# PROGRAMMER.net
KiCad netlist of a schematic drawn in Altium Designer
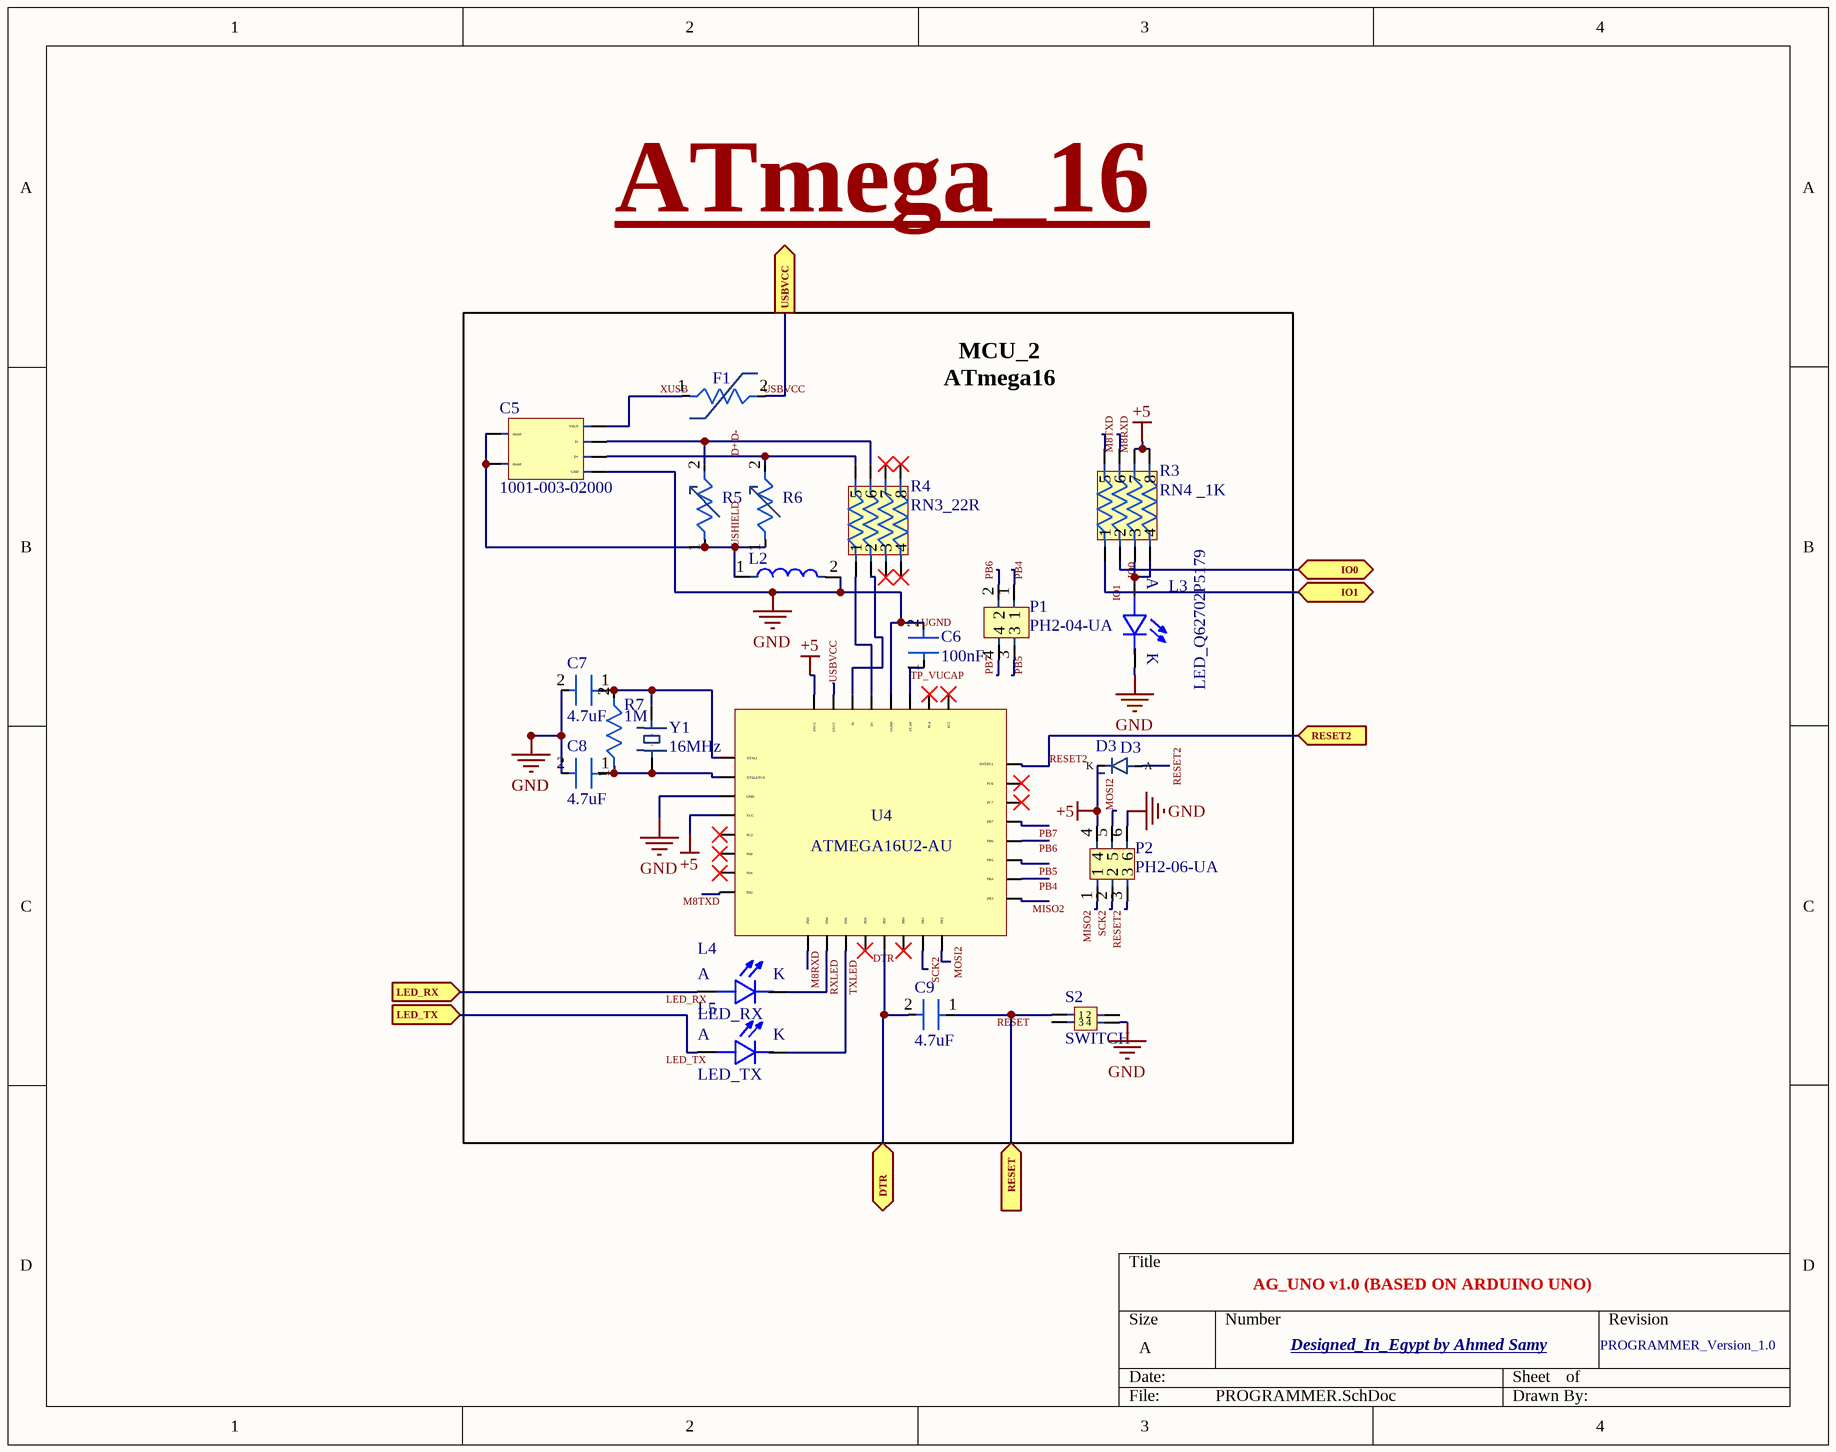
[diagram p0: PROGRAMMER.SchDoc]

(export (version "E")
  (design (tool "Eeschema 10.0.6"))
  (components
    (comp (ref "C5")
      (value "1001-003-02000")
      (footprint "1001-003-02000")
      (description "USB-B (USB TYPE-B) USB 1.1 Receptacle Connector 4 Position Through Hole, Right Angle")
      (libsource (lib "Task") (part "1001-003-02000"))
    )
    (comp (ref "C6")
      (value "100nF")
      (footprint "80-C0805C104M3R")
      (libsource (lib "Task") (part "80-C0805C104M3R"))
    )
    (comp (ref "C7")
      (value "4.7uF")
      (footprint "3372-0805W475K500CCTR-ND")
      (description "CAP.,SMD,0805,X5R,4.7UF,10%,50V")
      (libsource (lib "Task") (part "3372-0805W475K500CCTR-ND"))
    )
    (comp (ref "C8")
      (value "4.7uF")
      (footprint "3372-0805W475K500CCTR-ND")
      (description "CAP.,SMD,0805,X5R,4.7UF,10%,50V")
      (libsource (lib "Task") (part "3372-0805W475K500CCTR-ND"))
    )
    (comp (ref "C9")
      (value "4.7uF")
      (footprint "3372-0805W475K500CCTR-ND")
      (description "CAP.,SMD,0805,X5R,4.7UF,10%,50V")
      (libsource (lib "Task") (part "3372-0805W475K500CCTR-ND"))
    )
    (comp (ref "D3")
      (value "D3")
      (footprint "CD1206-S01575")
      (description "Diode 100 V 150mA Surface Mount 1206 [D2 UNO]")
      (libsource (lib "Task") (part "CD1206-S01575"))
    )
    (comp (ref "F1")
      (value "MF-MSMF050-2")
      (footprint "MF-MSMF050-2")
      (description "Polymeric PTC Resettable Fuse 15V 500 mA Ih Surface Mount 1812 (4532 Metric), Concave [UNO]")
      (libsource (lib "Task") (part "MF-MSMF050-2"))
    )
    (comp (ref "L2")
      (value "BLM21PG300SN1D")
      (footprint "BLM21PG300SN1D")
      (description "30 Ohms @ 100 MHz 1 Power Line Ferrite Bead 0805 (2012 Metric) 4A 14mOhm")
      (libsource (lib "Task") (part "BLM21PG300SN1D"))
    )
    (comp (ref "L3")
      (value "LED_Q62702P5179")
      (footprint "LED_Q62702P5179")
      (description "LED 0805")
      (libsource (lib "Task") (part "LED_Q62702P5179"))
    )
    (comp (ref "L4")
      (value "LED_RX")
      (footprint "LED_Q62702P5179")
      (description "LED 0805")
      (libsource (lib "") (part "LED_Q62702P5179_1"))
    )
    (comp (ref "L5")
      (value "LED_TX")
      (footprint "LED_Q62702P5179")
      (description "LED 0805")
      (libsource (lib "") (part "LED_Q62702P5179_1"))
    )
    (comp (ref "P1")
      (value "PH2-04-UA")
      (footprint "PH2-04-UA")
      (description "Connector Header Through Hole 4 position 0.100\" (2.54mm)")
      (libsource (lib "Task") (part "PH2-04-UA"))
    )
    (comp (ref "P2")
      (value "PH2-06-UA")
      (footprint "PH2-06-UA")
      (description "Connector Header Through Hole 6 position 0.100\" (2.54mm) [ICSP UNO]")
      (libsource (lib "Task") (part "PH2-06-UA"))
    )
    (comp (ref "R3")
      (value "RN4 _1K")
      (footprint "CAY16-103J4GLF")
      (libsource (lib "Task") (part "CAY16-103J4GLF"))
    )
    (comp (ref "R4")
      (value "RN3_22R")
      (footprint "CAY16-103J4GLF")
      (libsource (lib "Task") (part "CAY16-103J4GLF"))
    )
    (comp (ref "R5")
      (value "CG0603MLC-05E")
      (footprint "CG0603MLC-05E")
      (description "Varistor 1 Circuit Surface Mount, MLCV 0603 (1608 Metric)")
      (libsource (lib "Task") (part "CG0603MLC-05E"))
    )
    (comp (ref "R6")
      (value "CG0603MLC-05E")
      (footprint "CG0603MLC-05E")
      (description "Varistor 1 Circuit Surface Mount, MLCV 0603 (1608 Metric)")
      (libsource (lib "Task") (part "CG0603MLC-05E"))
    )
    (comp (ref "R7")
      (value "1M")
      (footprint "CRCW06031M00JNEAC")
      (description "1 MOhms ±5% 0.1W, 1/10W Chip Resistor 0603 (1608 Metric) Thick Film")
      (libsource (lib "Task") (part "CRCW06031M00JNEAC"))
    )
    (comp (ref "S2")
      (value "SWITCH")
      (footprint "B3SL-1002P")
      (description "Tactile Switch SPST-NO Top Actuated Surface Mount")
      (libsource (lib "Task") (part "B3SL-1002P"))
    )
    (comp (ref "U4")
      (value "ATMEGA16U2-AU")
      (footprint "ATMEGA16U2-AU")
      (description "AVR AVR® ATmega Microcontroller IC 8-Bit 16MHz 16KB (8K x 16) FLASH 32-TQFP (7x7)")
      (libsource (lib "Task") (part "ATMEGA16U2-AU"))
    )
    (comp (ref "Y1")
      (value "16MHz")
      (footprint "ECS-160-20-4X-DU")
      (description "16 MHz ±30ppm Crystal 20pF 40 Ohms HC-49/US")
      (libsource (lib "Task") (part "ECS-160-20-4X-DU"))
    )
  )
  (nets
    (net (code "1") (name "+5") (class "Default")
      (node (ref "D3") (pin "1") (pinfunction "K_1") (pintype "passive"))
      (node (ref "P2") (pin "4") (pinfunction "4_4") (pintype "passive"))
      (node (ref "R3") (pin "7") (pinfunction "7_7") (pintype "passive"))
      (node (ref "R3") (pin "8") (pinfunction "8_8") (pintype "passive"))
      (node (ref "U4") (pin "32") (pinfunction "AVCC_32") (pintype "passive"))
      (node (ref "U4") (pin "4") (pinfunction "VCC_4") (pintype "passive"))
    )
    (net (code "2") (name "/D+") (class "Default")
      (node (ref "C5") (pin "5") (pinfunction "D+_5") (pintype "bidirectional"))
      (node (ref "R4") (pin "5") (pinfunction "5_5") (pintype "passive"))
      (node (ref "R6") (pin "2") (pinfunction "2_2") (pintype "passive"))
    )
    (net (code "3") (name "/D-") (class "Default")
      (node (ref "C5") (pin "4") (pinfunction "D-_4") (pintype "bidirectional"))
      (node (ref "R4") (pin "6") (pinfunction "6_6") (pintype "passive"))
      (node (ref "R5") (pin "2") (pinfunction "2_2") (pintype "passive"))
    )
    (net (code "4") (name "/DTR") (class "Default")
      (node (ref "C9") (pin "2") (pintype "passive"))
      (node (ref "U4") (pin "13") (pinfunction "PD7_13") (pintype "bidirectional"))
    )
    (net (code "5") (name "/IO0") (class "Default")
      (node (ref "R3") (pin "2") (pinfunction "2_2") (pintype "passive"))
    )
    (net (code "6") (name "/IO1") (class "Default")
      (node (ref "R3") (pin "1") (pinfunction "1_1") (pintype "passive"))
    )
    (net (code "7") (name "/LED_RX") (class "Default")
      (node (ref "L4") (pin "A") (pinfunction "A_A") (pintype "passive"))
    )
    (net (code "8") (name "/LED_TX") (class "Default")
      (node (ref "L5") (pin "A") (pinfunction "A_A") (pintype "passive"))
    )
    (net (code "9") (name "/M8RXD") (class "Default")
      (node (ref "R3") (pin "6") (pinfunction "6_6") (pintype "passive"))
      (node (ref "U4") (pin "9") (pinfunction "PD3_9") (pintype "bidirectional"))
    )
    (net (code "10") (name "/M8TXD") (class "Default")
      (node (ref "R3") (pin "5") (pinfunction "5_5") (pintype "passive"))
      (node (ref "U4") (pin "8") (pinfunction "PD2_8") (pintype "bidirectional"))
    )
    (net (code "11") (name "/MISO2") (class "Default")
      (node (ref "P2") (pin "1") (pinfunction "1_1") (pintype "passive"))
      (node (ref "U4") (pin "17") (pinfunction "PB3_17") (pintype "bidirectional"))
    )
    (net (code "12") (name "/MOSI2") (class "Default")
      (node (ref "P2") (pin "5") (pinfunction "5_5") (pintype "passive"))
      (node (ref "U4") (pin "16") (pinfunction "PB2_16") (pintype "bidirectional"))
    )
    (net (code "13") (name "/PB4") (class "Default")
      (node (ref "P1") (pin "1") (pinfunction "1_1") (pintype "passive"))
      (node (ref "U4") (pin "18") (pinfunction "PB4_18") (pintype "bidirectional"))
    )
    (net (code "14") (name "/PB5") (class "Default")
      (node (ref "P1") (pin "3") (pinfunction "3_3") (pintype "passive"))
      (node (ref "U4") (pin "19") (pinfunction "PB5_19") (pintype "bidirectional"))
    )
    (net (code "15") (name "/PB6") (class "Default")
      (node (ref "P1") (pin "2") (pinfunction "2_2") (pintype "passive"))
      (node (ref "U4") (pin "20") (pinfunction "PB6_20") (pintype "bidirectional"))
    )
    (net (code "16") (name "/PB7") (class "Default")
      (node (ref "P1") (pin "4") (pinfunction "4_4") (pintype "passive"))
      (node (ref "U4") (pin "21") (pinfunction "PB7_21") (pintype "bidirectional"))
    )
    (net (code "17") (name "/RESET") (class "Default")
      (node (ref "C9") (pin "1") (pintype "passive"))
      (node (ref "S2") (pin "1") (pinfunction "1_1") (pintype "passive"))
    )
    (net (code "18") (name "/RESET2") (class "Default")
      (node (ref "D3") (pin "2") (pinfunction "A_2") (pintype "passive"))
      (node (ref "P2") (pin "3") (pinfunction "3_3") (pintype "passive"))
      (node (ref "U4") (pin "24") (pinfunction "RST/PC1_24") (pintype "bidirectional"))
    )
    (net (code "19") (name "/RXLED") (class "Default")
      (node (ref "L4") (pin "C") (pinfunction "C_C") (pintype "passive"))
      (node (ref "U4") (pin "10") (pinfunction "PD4_10") (pintype "bidirectional"))
    )
    (net (code "20") (name "/SCK2") (class "Default")
      (node (ref "P2") (pin "2") (pinfunction "2_2") (pintype "passive"))
      (node (ref "U4") (pin "15") (pinfunction "PB1_15") (pintype "bidirectional"))
    )
    (net (code "21") (name "/TP_VUCAP") (class "Default")
      (node (ref "C6") (pin "1") (pintype "passive"))
      (node (ref "U4") (pin "27") (pinfunction "UCAP_27") (pintype "passive"))
    )
    (net (code "22") (name "/TXLED") (class "Default")
      (node (ref "L5") (pin "C") (pinfunction "C_C") (pintype "passive"))
      (node (ref "U4") (pin "11") (pinfunction "PD5_11") (pintype "bidirectional"))
    )
    (net (code "23") (name "/USBVCC") (class "Default")
      (node (ref "F1") (pin "2") (pinfunction "2_2") (pintype "passive"))
      (node (ref "U4") (pin "31") (pinfunction "UVCC_31") (pintype "passive"))
    )
    (net (code "24") (name "/USHIELD") (class "Default")
      (node (ref "C5") (pin "1") (pinfunction "shield_1") (pintype "passive"))
      (node (ref "C5") (pin "2") (pinfunction "shield_2") (pintype "passive"))
      (node (ref "L2") (pin "1") (pinfunction "1_1") (pintype "passive"))
      (node (ref "R5") (pin "1") (pinfunction "1_1") (pintype "passive"))
      (node (ref "R6") (pin "1") (pinfunction "1_1") (pintype "passive"))
    )
    (net (code "25") (name "/XUSB") (class "Default")
      (node (ref "C5") (pin "3") (pinfunction "VBUS_3") (pintype "power_in"))
      (node (ref "F1") (pin "1") (pinfunction "1_1") (pintype "passive"))
    )
    (net (code "26") (name "GND") (class "Default")
      (node (ref "C5") (pin "6") (pinfunction "GND_6") (pintype "power_in"))
      (node (ref "C6") (pin "2") (pintype "passive"))
      (node (ref "C7") (pin "2") (pintype "passive"))
      (node (ref "C8") (pin "2") (pintype "passive"))
      (node (ref "L2") (pin "2") (pinfunction "2_2") (pintype "passive"))
      (node (ref "L3") (pin "C") (pinfunction "C_C") (pintype "passive"))
      (node (ref "P2") (pin "6") (pinfunction "6_6") (pintype "passive"))
      (node (ref "S2") (pin "4") (pinfunction "4_4") (pintype "passive"))
      (node (ref "U4") (pin "28") (pinfunction "UGND_28") (pintype "power_in"))
      (node (ref "U4") (pin "3") (pinfunction "GND_3") (pintype "power_in"))
    )
    (net (code "27") (name "Net-(L3-PadA)") (class "Default")
      (node (ref "L3") (pin "A") (pinfunction "A_A") (pintype "passive"))
      (node (ref "R3") (pin "3") (pinfunction "3_3") (pintype "passive"))
      (node (ref "R3") (pin "4") (pinfunction "4_4") (pintype "passive"))
    )
    (net (code "28") (name "Net-(U4-D+)") (class "Default")
      (node (ref "R4") (pin "1") (pinfunction "1_1") (pintype "passive"))
      (node (ref "U4") (pin "29") (pinfunction "D+_29") (pintype "bidirectional"))
    )
    (net (code "29") (name "Net-(U4-D-)") (class "Default")
      (node (ref "R4") (pin "2") (pinfunction "2_2") (pintype "passive"))
      (node (ref "U4") (pin "30") (pinfunction "D-_30") (pintype "bidirectional"))
    )
    (net (code "30") (name "Net-(U4-XTAL1)") (class "Default")
      (node (ref "C7") (pin "1") (pintype "passive"))
      (node (ref "R7") (pin "2") (pinfunction "2_2") (pintype "passive"))
      (node (ref "U4") (pin "1") (pinfunction "XTAL1_1") (pintype "input"))
      (node (ref "Y1") (pin "1") (pinfunction "1_1") (pintype "passive"))
    )
    (net (code "31") (name "Net-(U4-XTAL2{slash}PC0)") (class "Default")
      (node (ref "C8") (pin "1") (pintype "passive"))
      (node (ref "R7") (pin "1") (pinfunction "1_1") (pintype "passive"))
      (node (ref "U4") (pin "2") (pinfunction "XTAL2/PC0_2") (pintype "bidirectional"))
      (node (ref "Y1") (pin "2") (pinfunction "2_2") (pintype "passive"))
    )
    (net (code "32") (name "unconnected-(R4-Pad3)") (class "Default")
      (node (ref "R4") (pin "3") (pinfunction "3_3") (pintype "passive+no_connect"))
    )
    (net (code "33") (name "unconnected-(R4-Pad4)") (class "Default")
      (node (ref "R4") (pin "4") (pinfunction "4_4") (pintype "passive+no_connect"))
    )
    (net (code "34") (name "unconnected-(R4-Pad7)") (class "Default")
      (node (ref "R4") (pin "7") (pinfunction "7_7") (pintype "passive+no_connect"))
    )
    (net (code "35") (name "unconnected-(R4-Pad8)") (class "Default")
      (node (ref "R4") (pin "8") (pinfunction "8_8") (pintype "passive+no_connect"))
    )
    (net (code "36") (name "unconnected-(S2-Pad2)") (class "Default")
      (node (ref "S2") (pin "2") (pinfunction "2_2") (pintype "passive"))
    )
    (net (code "37") (name "unconnected-(S2-Pad3)") (class "Default")
      (node (ref "S2") (pin "3") (pinfunction "3_3") (pintype "passive"))
    )
    (net (code "38") (name "unconnected-(U4-PB0-Pad14)") (class "Default")
      (node (ref "U4") (pin "14") (pinfunction "PB0_14") (pintype "bidirectional+no_connect"))
    )
    (net (code "39") (name "unconnected-(U4-PC2-Pad5)") (class "Default")
      (node (ref "U4") (pin "5") (pinfunction "PC2_5") (pintype "bidirectional+no_connect"))
    )
    (net (code "40") (name "unconnected-(U4-PC4-Pad26)") (class "Default")
      (node (ref "U4") (pin "26") (pinfunction "PC4_26") (pintype "bidirectional+no_connect"))
    )
    (net (code "41") (name "unconnected-(U4-PC5-Pad25)") (class "Default")
      (node (ref "U4") (pin "25") (pinfunction "PC5_25") (pintype "bidirectional+no_connect"))
    )
    (net (code "42") (name "unconnected-(U4-PC6-Pad23)") (class "Default")
      (node (ref "U4") (pin "23") (pinfunction "PC6_23") (pintype "bidirectional+no_connect"))
    )
    (net (code "43") (name "unconnected-(U4-PC7-Pad22)") (class "Default")
      (node (ref "U4") (pin "22") (pinfunction "PC7_22") (pintype "bidirectional+no_connect"))
    )
    (net (code "44") (name "unconnected-(U4-PD0-Pad6)") (class "Default")
      (node (ref "U4") (pin "6") (pinfunction "PD0_6") (pintype "bidirectional+no_connect"))
    )
    (net (code "45") (name "unconnected-(U4-PD1-Pad7)") (class "Default")
      (node (ref "U4") (pin "7") (pinfunction "PD1_7") (pintype "bidirectional+no_connect"))
    )
    (net (code "46") (name "unconnected-(U4-PD6-Pad12)") (class "Default")
      (node (ref "U4") (pin "12") (pinfunction "PD6_12") (pintype "bidirectional+no_connect"))
    )
  )
)
